# AWG_CPCIS_Connectors_P1_P6.net
KiCad netlist of a schematic drawn in Altium Designer
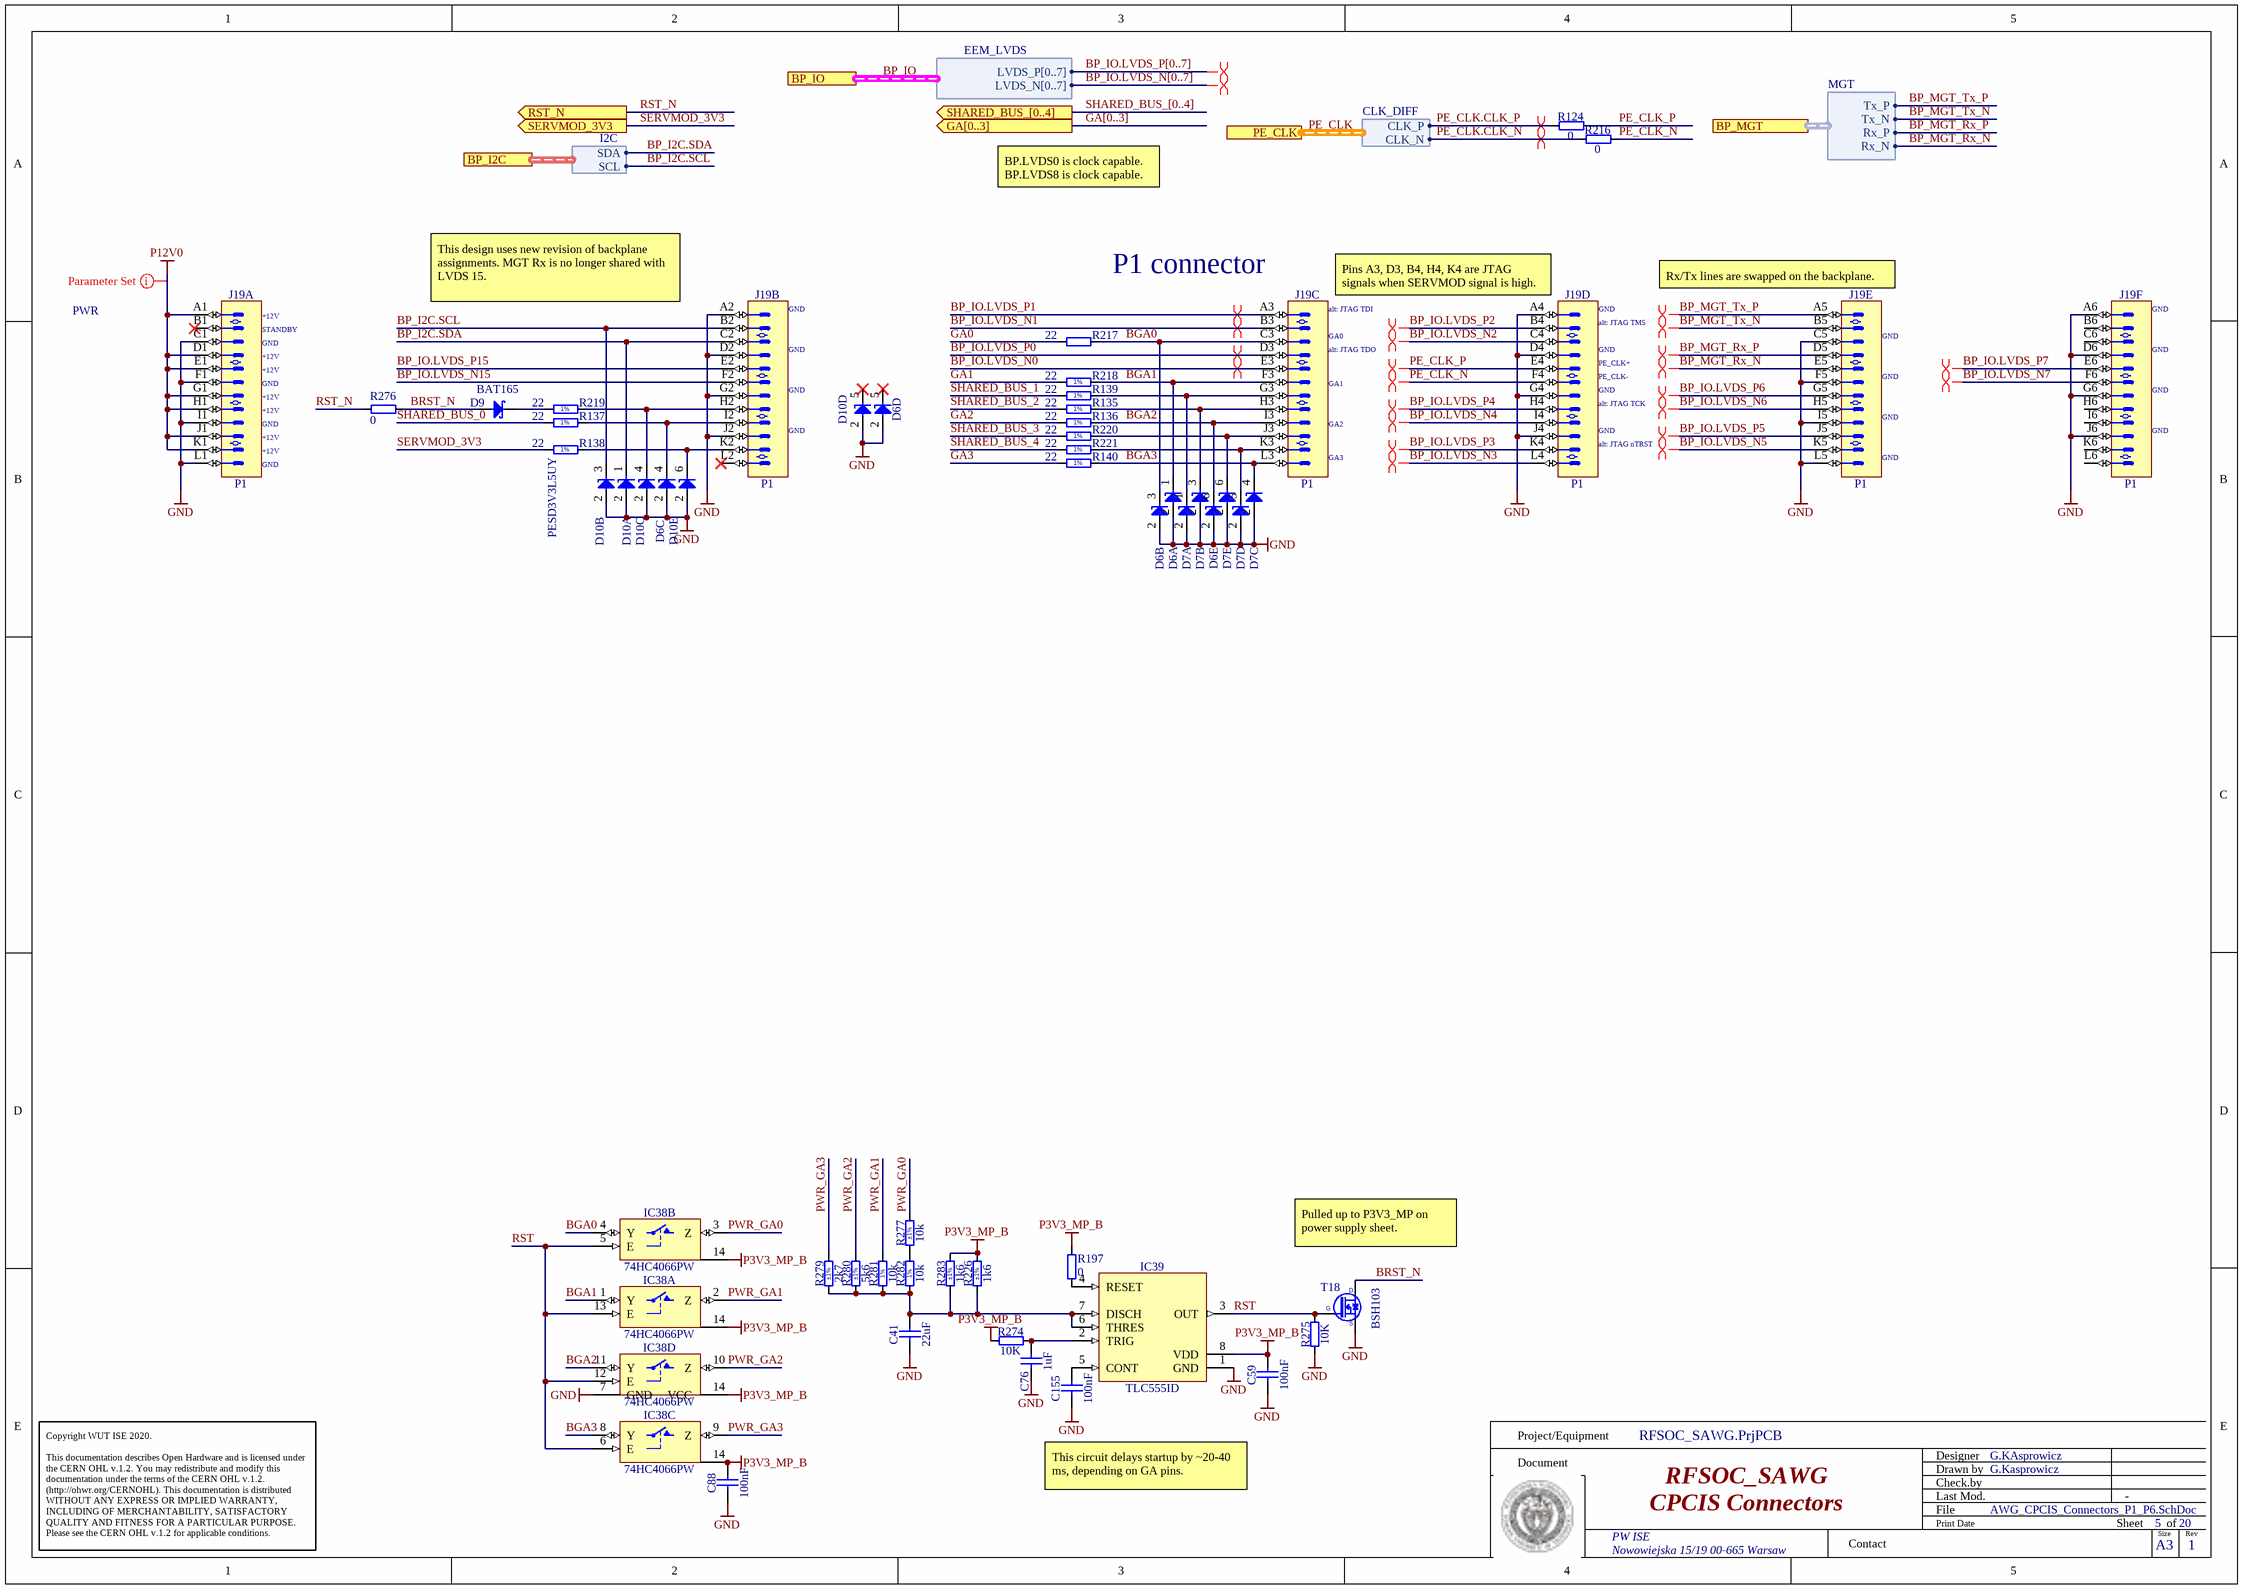
[diagram p0: AWG_CPCIS_Connectors_P1_P6.SchDoc]

(export (version "E")
  (design (tool "Eeschema 10.0.6"))
  (components
    (comp (ref "C41")
      (value "22uF")
      (footprint "CAPC1608X90N")
      (description "Non-polarised capacitor")
      (fields
        (field (name "MANUFACTURER") "GENERIC")
        (field (name "PART NUMBER") "CC0603_22UF_6.3V_20%_X5R")
        (field (name "AUTHOR") "CERN DEM JLC")
      )
      (libsource (lib "Capacitors") (part "Capacitor - non polarized"))
    )
    (comp (ref "C59")
      (value "100nF")
      (footprint "CAPC1005X55N")
      (description "Non-polarised capacitor")
      (fields
        (field (name "PART NUMBER") "CC0402_100NF_16V_10%_X5R")
        (field (name "VOLTAGE") "16V")
        (field (name "AUTHOR") "CERN DEM JLC")
      )
      (libsource (lib "Capacitors") (part "Capacitor - non polarized"))
    )
    (comp (ref "C76")
      (value "1uF")
      (footprint "CAPC1005X55N")
      (description "Non-polarised capacitor")
      (fields
        (field (name "PART NUMBER") "CC0402_1UF_16V_10%_X5R")
        (field (name "VOLTAGE") "16V")
        (field (name "AUTHOR") "CERN DEM JLC")
      )
      (libsource (lib "Capacitors") (part "Capacitor - non polarized"))
    )
    (comp (ref "C88")
      (value "100nF")
      (footprint "CAPC1005X55N")
      (description "Non-polarised capacitor")
      (fields
        (field (name "PART NUMBER") "CC0402_100NF_16V_10%_X5R")
        (field (name "VOLTAGE") "16V")
        (field (name "AUTHOR") "CERN DEM JLC")
      )
      (libsource (lib "Capacitors") (part "Capacitor - non polarized"))
    )
    (comp (ref "C155")
      (value "100nF")
      (footprint "CAPC1005X55N")
      (description "Non-polarised capacitor")
      (fields
        (field (name "PART NUMBER") "CC0402_100NF_16V_10%_X5R")
        (field (name "VOLTAGE") "16V")
        (field (name "AUTHOR") "CERN DEM JLC")
      )
      (libsource (lib "Capacitors") (part "Capacitor - non polarized"))
    )
    (comp (ref "D6")
      (value "PESD3V3L5UY")
      (footprint "SOT65P210X110-6N")
      (description "Fivefold ESD Protection Diode Arrays")
      (fields
        (field (name "VOLTAGE") "3.3V")
        (field (name "POWER") "200W")
        (field (name "AUTHOR") "CERN DEM WB")
      )
      (libsource (lib "ICs And Semiconductors") (part "PESD Array 5diodes 6pins Common anode2"))
    )
    (comp (ref "D7")
      (value "PESD3V3L5UY")
      (footprint "SOT65P210X110-6N")
      (description "Fivefold ESD Protection Diode Arrays")
      (fields
        (field (name "VOLTAGE") "3.3V")
        (field (name "POWER") "200W")
        (field (name "AUTHOR") "CERN DEM WB")
      )
      (libsource (lib "ICs And Semiconductors") (part "PESD Array 5diodes 6pins Common anode2"))
    )
    (comp (ref "D9")
      (value "BAT165")
      (footprint "SOD2512X110N")
      (description "Schottky Diode")
      (fields
        (field (name "MANUFACTURER") "INFINEON")
        (field (name "VOLTAGE") "40V")
        (field (name "AUTHOR") "CERN DEM JLC")
      )
      (libsource (lib "ICs And Semiconductors") (part "Diode Schottky"))
    )
    (comp (ref "D10")
      (value "PESD3V3L5UY")
      (footprint "SOT65P210X110-6N")
      (description "Fivefold ESD Protection Diode Arrays")
      (fields
        (field (name "VOLTAGE") "3.3V")
        (field (name "POWER") "200W")
        (field (name "AUTHOR") "CERN DEM WB")
      )
      (libsource (lib "ICs And Semiconductors") (part "PESD Array 5diodes 6pins Common anode2"))
    )
    (comp (ref "IC38")
      (value "74HC4066PW")
      (footprint "SOP65P640X110-14N")
      (fields (field (name "MANUFACTURER") "NXP SEMICONDUCTORS") (field (name "AUTHOR") "CERN DEM JLC"))
      (libsource (lib "ICs And Semiconductors") (part "4066"))
    )
    (comp (ref "IC39")
      (value "TLC555ID")
      (footprint "SOIC127P600X175-8N")
      (description "LinCMOS Timer")
      (fields (field (name "MANUFACTURER") "TEXAS INSTRUMENTS") (field (name "AUTHOR") "CERN DEM JMW"))
      (libsource (lib "ICs And Semiconductors") (part "TLC555"))
    )
    (comp (ref "J19")
      (value "P1")
      (footprint "AMPHENOL_10052825-101LF")
      (description "72 Contacts Header, 6 Columns, 4 Pairs per Column")
      (fields
        (field (name "PART NUMBER") "AMPHENOL_10052825-101LF")
        (field (name "MANUFACTURER") "AMPHENOL")
        (field (name "AUTHOR") "CERN DEM MR")
      )
      (libsource (lib "Connectors") (part "AMPHENOL_10052825-101LF"))
    )
    (comp (ref "R124")
      (value "0")
      (footprint "RESC0603X28N")
      (description "Resistor")
      (fields
        (field (name "PART NUMBER") "R0201_0R_JUMPER")
        (field (name "MANUFACTURER") "GENERIC")
        (field (name "AUTHOR") "CERN DEM JLC")
      )
      (libsource (lib "Resistors") (part "Resistor"))
    )
    (comp (ref "R135")
      (value "22")
      (footprint "RESC1005X40N")
      (description "Resistor - 1%")
      (fields
        (field (name "PART NUMBER") "R0402_22R_1%_0.0625W_100PPM")
        (field (name "POWER") "0.0625W")
        (field (name "AUTHOR") "CERN DEM JLC")
      )
      (libsource (lib "Resistors") (part "Resistor - 1%"))
    )
    (comp (ref "R136")
      (value "22")
      (footprint "RESC1005X40N")
      (description "Resistor - 1%")
      (fields
        (field (name "PART NUMBER") "R0402_22R_1%_0.0625W_100PPM")
        (field (name "POWER") "0.0625W")
        (field (name "AUTHOR") "CERN DEM JLC")
      )
      (libsource (lib "Resistors") (part "Resistor - 1%"))
    )
    (comp (ref "R137")
      (value "22")
      (footprint "RESC1005X40N")
      (description "Resistor - 1%")
      (fields
        (field (name "PART NUMBER") "R0402_22R_1%_0.0625W_100PPM")
        (field (name "POWER") "0.0625W")
        (field (name "AUTHOR") "CERN DEM JLC")
      )
      (libsource (lib "Resistors") (part "Resistor - 1%"))
    )
    (comp (ref "R138")
      (value "22")
      (footprint "RESC1005X40N")
      (description "Resistor - 1%")
      (fields
        (field (name "PART NUMBER") "R0402_22R_1%_0.0625W_100PPM")
        (field (name "POWER") "0.0625W")
        (field (name "AUTHOR") "CERN DEM JLC")
      )
      (libsource (lib "Resistors") (part "Resistor - 1%"))
    )
    (comp (ref "R139")
      (value "22")
      (footprint "RESC1005X40N")
      (description "Resistor - 1%")
      (fields
        (field (name "PART NUMBER") "R0402_22R_1%_0.0625W_100PPM")
        (field (name "POWER") "0.0625W")
        (field (name "AUTHOR") "CERN DEM JLC")
      )
      (libsource (lib "Resistors") (part "Resistor - 1%"))
    )
    (comp (ref "R140")
      (value "22")
      (footprint "RESC1005X40N")
      (description "Resistor - 1%")
      (fields
        (field (name "PART NUMBER") "R0402_22R_1%_0.0625W_100PPM")
        (field (name "POWER") "0.0625W")
        (field (name "AUTHOR") "CERN DEM JLC")
      )
      (libsource (lib "Resistors") (part "Resistor - 1%"))
    )
    (comp (ref "R197")
      (value "0")
      (footprint "RESC1005X40N")
      (description "Resistor")
      (fields
        (field (name "PART NUMBER") "R0402_0R_JUMPER")
        (field (name "MANUFACTURER") "GENERIC")
        (field (name "AUTHOR") "CERN DEM JLC")
      )
      (libsource (lib "Resistors") (part "Resistor"))
    )
    (comp (ref "R216")
      (value "0")
      (footprint "RESC0603X28N")
      (description "Resistor")
      (fields
        (field (name "PART NUMBER") "R0201_0R_JUMPER")
        (field (name "MANUFACTURER") "GENERIC")
        (field (name "AUTHOR") "CERN DEM JLC")
      )
      (libsource (lib "Resistors") (part "Resistor"))
    )
    (comp (ref "R217")
      (value "22")
      (footprint "RESC1005X40N")
      (description "Resistor - 1%")
      (fields
        (field (name "PART NUMBER") "R0402_22R_1%_0.0625W_100PPM")
        (field (name "POWER") "0.0625W")
        (field (name "AUTHOR") "CERN DEM JLC")
      )
      (libsource (lib "Resistors") (part "Resistor - 1%"))
    )
    (comp (ref "R218")
      (value "22")
      (footprint "RESC1005X40N")
      (description "Resistor - 1%")
      (fields
        (field (name "PART NUMBER") "R0402_22R_1%_0.0625W_100PPM")
        (field (name "POWER") "0.0625W")
        (field (name "AUTHOR") "CERN DEM JLC")
      )
      (libsource (lib "Resistors") (part "Resistor - 1%"))
    )
    (comp (ref "R219")
      (value "22")
      (footprint "RESC1005X40N")
      (description "Resistor - 1%")
      (fields
        (field (name "PART NUMBER") "R0402_22R_1%_0.0625W_100PPM")
        (field (name "POWER") "0.0625W")
        (field (name "AUTHOR") "CERN DEM JLC")
      )
      (libsource (lib "Resistors") (part "Resistor - 1%"))
    )
    (comp (ref "R220")
      (value "22")
      (footprint "RESC1005X40N")
      (description "Resistor - 1%")
      (fields
        (field (name "PART NUMBER") "R0402_22R_1%_0.0625W_100PPM")
        (field (name "POWER") "0.0625W")
        (field (name "AUTHOR") "CERN DEM JLC")
      )
      (libsource (lib "Resistors") (part "Resistor - 1%"))
    )
    (comp (ref "R221")
      (value "22")
      (footprint "RESC1005X40N")
      (description "Resistor - 1%")
      (fields
        (field (name "PART NUMBER") "R0402_22R_1%_0.0625W_100PPM")
        (field (name "POWER") "0.0625W")
        (field (name "AUTHOR") "CERN DEM JLC")
      )
      (libsource (lib "Resistors") (part "Resistor - 1%"))
    )
    (comp (ref "R226")
      (value "1k6")
      (footprint "RESC1005X40N")
      (description "Resistor - 1%")
      (fields
        (field (name "PART NUMBER") "R0402_1K6_1%_0.0625W_100PPM")
        (field (name "POWER") "0.0625W")
        (field (name "TOLERANCE") "±1%")
        (field (name "AUTHOR") "CERN DEM JLC")
      )
      (libsource (lib "Resistors") (part "Resistor - 1%"))
    )
    (comp (ref "R274")
      (value "10K")
      (footprint "RESC1005X40N")
      (description "Resistor - 1%")
      (fields
        (field (name "PART NUMBER") "R0402_10K_1%_0.0625W_100PPM")
        (field (name "POWER") "0.0625W")
        (field (name "AUTHOR") "CERN DEM JLC")
      )
      (libsource (lib "Resistors") (part "Resistor - 1%"))
    )
    (comp (ref "R275")
      (value "10K")
      (footprint "RESC1005X40N")
      (description "Resistor - 1%")
      (fields
        (field (name "PART NUMBER") "R0402_10K_1%_0.0625W_100PPM")
        (field (name "POWER") "0.0625W")
        (field (name "AUTHOR") "CERN DEM JLC")
      )
      (libsource (lib "Resistors") (part "Resistor - 1%"))
    )
    (comp (ref "R276")
      (value "0")
      (footprint "RESC1005X40N")
      (description "Resistor")
      (fields
        (field (name "PART NUMBER") "R0402_0R_JUMPER")
        (field (name "MANUFACTURER") "GENERIC")
        (field (name "AUTHOR") "CERN DEM JLC")
      )
      (libsource (lib "Resistors") (part "Resistor"))
    )
    (comp (ref "R277")
      (value "10k")
      (footprint "RESC1005X40N")
      (description "Resistor - 1%")
      (fields
        (field (name "PART NUMBER") "R0402_10K_1%_0.0625W_100PPM")
        (field (name "POWER") "0.0625W")
        (field (name "TOLERANCE") "±1%")
        (field (name "AUTHOR") "CERN DEM JLC")
      )
      (libsource (lib "Resistors") (part "Resistor - 1%"))
    )
    (comp (ref "R279")
      (value "2k7")
      (footprint "RESC1608X55N")
      (description "Resistor - 1%")
      (fields
        (field (name "PART NUMBER") "R0603_2K7_1%_0.1W_100PPM")
        (field (name "POWER") "0.1W")
        (field (name "TOLERANCE") "±1%")
        (field (name "AUTHOR") "CERN DEM JLC")
      )
      (libsource (lib "") (part "Resistor - 1%_1"))
    )
    (comp (ref "R280")
      (value "5k6")
      (footprint "RESC1005X40N")
      (description "Resistor - 1%")
      (fields
        (field (name "PART NUMBER") "R0402_5K6_1%_0.0625W_100PPM")
        (field (name "POWER") "0.0625W")
        (field (name "TOLERANCE") "±1%")
        (field (name "AUTHOR") "CERN DEM JLC")
      )
      (libsource (lib "Resistors") (part "Resistor - 1%"))
    )
    (comp (ref "R281")
      (value "10k")
      (footprint "RESC1005X40N")
      (description "Resistor - 1%")
      (fields
        (field (name "PART NUMBER") "R0402_1K_1%_0.0625W_100PPM")
        (field (name "POWER") "0.0625W")
        (field (name "AUTHOR") "CERN DEM JLC")
      )
      (libsource (lib "Resistors") (part "Resistor - 1%"))
    )
    (comp (ref "R282")
      (value "10k")
      (footprint "RESC1005X40N")
      (description "Resistor - 1%")
      (fields
        (field (name "PART NUMBER") "R0402_1K_1%_0.0625W_100PPM")
        (field (name "POWER") "0.0625W")
        (field (name "AUTHOR") "CERN DEM JLC")
      )
      (libsource (lib "Resistors") (part "Resistor - 1%"))
    )
    (comp (ref "R283")
      (value "1k6")
      (footprint "RESC1005X40N")
      (description "Resistor - 1%")
      (fields
        (field (name "PART NUMBER") "R0402_1K6_1%_0.0625W_100PPM")
        (field (name "POWER") "0.0625W")
        (field (name "TOLERANCE") "±1%")
        (field (name "AUTHOR") "CERN DEM JLC")
      )
      (libsource (lib "Resistors") (part "Resistor - 1%"))
    )
    (comp (ref "T18")
      (value "BSH103")
      (footprint "SOT95P230X110-3N")
      (description "N-CHANNEL MOSFET WITH DIODE")
      (fields (field (name "MANUFACTURER") "NEXPERIA") (field (name "AUTHOR") "CERN DEM JLC"))
      (libsource (lib "ICs And Semiconductors") (part "N-MOSFET-D 1G 2S 3D"))
    )
  )
  (nets
    (net (code "5") (name "/BGA0") (class "Default")
      (node (ref "D6") (pin "3") (pinfunction "C_3") (pintype "passive"))
      (node (ref "IC38") (pin "4") (pinfunction "Y_4") (pintype "bidirectional"))
      (node (ref "J19") (pin "C3") (pinfunction "C3_C3") (pintype "bidirectional"))
      (node (ref "R217") (pin "2") (pinfunction "2_2") (pintype "passive"))
    )
    (net (code "6") (name "/BGA1") (class "Default")
      (node (ref "D6") (pin "1") (pinfunction "C_1") (pintype "passive"))
      (node (ref "IC38") (pin "1") (pinfunction "Y_1") (pintype "bidirectional"))
      (node (ref "J19") (pin "F3") (pinfunction "F3_F3") (pintype "bidirectional"))
      (node (ref "R218") (pin "2") (pinfunction "2_2") (pintype "passive"))
    )
    (net (code "7") (name "/BGA2") (class "Default")
      (node (ref "D6") (pin "6") (pinfunction "C_6") (pintype "passive"))
      (node (ref "IC38") (pin "11") (pinfunction "Y_11") (pintype "bidirectional"))
      (node (ref "J19") (pin "I3") (pinfunction "I3_I3") (pintype "bidirectional"))
      (node (ref "R136") (pin "2") (pinfunction "2_2") (pintype "passive"))
    )
    (net (code "8") (name "/BGA3") (class "Default")
      (node (ref "D7") (pin "4") (pinfunction "C_4") (pintype "passive"))
      (node (ref "IC38") (pin "8") (pinfunction "Y_8") (pintype "bidirectional"))
      (node (ref "J19") (pin "L3") (pinfunction "L3_L3") (pintype "bidirectional"))
      (node (ref "R140") (pin "2") (pinfunction "2_2") (pintype "passive"))
    )
    (net (code "9") (name "/BP_I2C.SCL") (class "Default")
      (node (ref "D10") (pin "3") (pinfunction "C_3") (pintype "passive"))
      (node (ref "J19") (pin "B2") (pinfunction "B2_B2") (pintype "bidirectional"))
    )
    (net (code "10") (name "/BP_I2C.SDA") (class "Default")
      (node (ref "D10") (pin "1") (pinfunction "C_1") (pintype "passive"))
      (node (ref "J19") (pin "C2") (pinfunction "C2_C2") (pintype "bidirectional"))
    )
    (net (code "11") (name "/BP_IO.LVDS_N0") (class "Default")
      (node (ref "J19") (pin "E3") (pinfunction "E3_E3") (pintype "bidirectional"))
    )
    (net (code "12") (name "/BP_IO.LVDS_N1") (class "Default")
      (node (ref "J19") (pin "B3") (pinfunction "B3_B3") (pintype "bidirectional"))
    )
    (net (code "13") (name "/BP_IO.LVDS_N2") (class "Default")
      (node (ref "J19") (pin "C4") (pinfunction "C4_C4") (pintype "bidirectional"))
    )
    (net (code "14") (name "/BP_IO.LVDS_N3") (class "Default")
      (node (ref "J19") (pin "L4") (pinfunction "L4_L4") (pintype "bidirectional"))
    )
    (net (code "15") (name "/BP_IO.LVDS_N4") (class "Default")
      (node (ref "J19") (pin "I4") (pinfunction "I4_I4") (pintype "bidirectional"))
    )
    (net (code "16") (name "/BP_IO.LVDS_N5") (class "Default")
      (node (ref "J19") (pin "K5") (pinfunction "K5_K5") (pintype "bidirectional"))
    )
    (net (code "17") (name "/BP_IO.LVDS_N6") (class "Default")
      (node (ref "J19") (pin "H5") (pinfunction "H5_H5") (pintype "bidirectional"))
    )
    (net (code "18") (name "/BP_IO.LVDS_N7") (class "Default")
      (node (ref "J19") (pin "F6") (pinfunction "F6_F6") (pintype "bidirectional"))
    )
    (net (code "19") (name "/BP_IO.LVDS_N15") (class "Default")
      (node (ref "J19") (pin "F2") (pinfunction "F2_F2") (pintype "bidirectional"))
    )
    (net (code "20") (name "/BP_IO.LVDS_P0") (class "Default")
      (node (ref "J19") (pin "D3") (pinfunction "D3_D3") (pintype "bidirectional"))
    )
    (net (code "21") (name "/BP_IO.LVDS_P1") (class "Default")
      (node (ref "J19") (pin "A3") (pinfunction "A3_A3") (pintype "bidirectional"))
    )
    (net (code "22") (name "/BP_IO.LVDS_P2") (class "Default")
      (node (ref "J19") (pin "B4") (pinfunction "B4_B4") (pintype "bidirectional"))
    )
    (net (code "23") (name "/BP_IO.LVDS_P3") (class "Default")
      (node (ref "J19") (pin "K4") (pinfunction "K4_K4") (pintype "bidirectional"))
    )
    (net (code "24") (name "/BP_IO.LVDS_P4") (class "Default")
      (node (ref "J19") (pin "H4") (pinfunction "H4_H4") (pintype "bidirectional"))
    )
    (net (code "25") (name "/BP_IO.LVDS_P5") (class "Default")
      (node (ref "J19") (pin "J5") (pinfunction "J5_J5") (pintype "bidirectional"))
    )
    (net (code "26") (name "/BP_IO.LVDS_P6") (class "Default")
      (node (ref "J19") (pin "G5") (pinfunction "G5_G5") (pintype "bidirectional"))
    )
    (net (code "27") (name "/BP_IO.LVDS_P7") (class "Default")
      (node (ref "J19") (pin "E6") (pinfunction "E6_E6") (pintype "bidirectional"))
    )
    (net (code "28") (name "/BP_IO.LVDS_P15") (class "Default")
      (node (ref "J19") (pin "E2") (pinfunction "E2_E2") (pintype "bidirectional"))
    )
    (net (code "30") (name "/BP_MGT_Rx_N") (class "Default")
      (node (ref "J19") (pin "E5") (pinfunction "E5_E5") (pintype "bidirectional"))
    )
    (net (code "31") (name "/BP_MGT_Rx_P") (class "Default")
      (node (ref "J19") (pin "D5") (pinfunction "D5_D5") (pintype "bidirectional"))
    )
    (net (code "32") (name "/BP_MGT_Tx_N") (class "Default")
      (node (ref "J19") (pin "B5") (pinfunction "B5_B5") (pintype "bidirectional"))
    )
    (net (code "33") (name "/BP_MGT_Tx_P") (class "Default")
      (node (ref "J19") (pin "A5") (pinfunction "A5_A5") (pintype "bidirectional"))
    )
    (net (code "34") (name "/BRST_N") (class "Default")
      (node (ref "D9") (pin "2") (pinfunction "A_2") (pintype "passive"))
      (node (ref "R276") (pin "1") (pinfunction "1_1") (pintype "passive"))
      (node (ref "T18") (pin "3") (pinfunction "D_3") (pintype "passive"))
    )
    (net (code "35") (name "/GA0") (class "Default")
      (node (ref "R217") (pin "1") (pinfunction "1_1") (pintype "passive"))
    )
    (net (code "36") (name "/GA1") (class "Default")
      (node (ref "R218") (pin "1") (pinfunction "1_1") (pintype "passive"))
    )
    (net (code "37") (name "/GA2") (class "Default")
      (node (ref "R136") (pin "1") (pinfunction "1_1") (pintype "passive"))
    )
    (net (code "38") (name "/GA3") (class "Default")
      (node (ref "R140") (pin "1") (pinfunction "1_1") (pintype "passive"))
    )
    (net (code "40") (name "/PE_CLK.CLK_N") (class "Default")
      (node (ref "R216") (pin "1") (pinfunction "1_1") (pintype "passive"))
    )
    (net (code "41") (name "/PE_CLK.CLK_P") (class "Default")
      (node (ref "R124") (pin "1") (pinfunction "1_1") (pintype "passive"))
    )
    (net (code "42") (name "/PE_CLK_N") (class "Default")
      (node (ref "J19") (pin "F4") (pinfunction "F4_F4") (pintype "bidirectional"))
      (node (ref "R216") (pin "2") (pinfunction "2_2") (pintype "passive"))
    )
    (net (code "43") (name "/PE_CLK_P") (class "Default")
      (node (ref "J19") (pin "E4") (pinfunction "E4_E4") (pintype "bidirectional"))
      (node (ref "R124") (pin "2") (pinfunction "2_2") (pintype "passive"))
    )
    (net (code "45") (name "/PWR_GA0") (class "Default")
      (node (ref "IC38") (pin "3") (pinfunction "Z_3") (pintype "bidirectional"))
      (node (ref "R277") (pin "2") (pinfunction "2_2") (pintype "passive"))
    )
    (net (code "46") (name "/PWR_GA1") (class "Default")
      (node (ref "IC38") (pin "2") (pinfunction "Z_2") (pintype "bidirectional"))
      (node (ref "R281") (pin "2") (pinfunction "2_2") (pintype "passive"))
    )
    (net (code "47") (name "/PWR_GA2") (class "Default")
      (node (ref "IC38") (pin "10") (pinfunction "Z_10") (pintype "bidirectional"))
      (node (ref "R280") (pin "2") (pinfunction "2_2") (pintype "passive"))
    )
    (net (code "48") (name "/PWR_GA3") (class "Default")
      (node (ref "IC38") (pin "9") (pinfunction "Z_9") (pintype "bidirectional"))
      (node (ref "R279") (pin "2") (pinfunction "2_2") (pintype "passive"))
    )
    (net (code "49") (name "/RST") (class "Default")
      (node (ref "IC38") (pin "12") (pinfunction "E_12") (pintype "input"))
      (node (ref "IC38") (pin "13") (pinfunction "E_13") (pintype "input"))
      (node (ref "IC38") (pin "5") (pinfunction "E_5") (pintype "input"))
      (node (ref "IC38") (pin "6") (pinfunction "E_6") (pintype "input"))
      (node (ref "IC39") (pin "3") (pinfunction "OUT_3") (pintype "output"))
      (node (ref "R275") (pin "2") (pinfunction "2_2") (pintype "passive"))
      (node (ref "T18") (pin "1") (pinfunction "G_1") (pintype "passive"))
    )
    (net (code "50") (name "/RST_N") (class "Default")
      (node (ref "R276") (pin "2") (pinfunction "2_2") (pintype "passive"))
    )
    (net (code "51") (name "/SERVMOD_3V3") (class "Default")
      (node (ref "R138") (pin "1") (pinfunction "1_1") (pintype "passive"))
    )
    (net (code "52") (name "/SHARED_BUS_0") (class "Default")
      (node (ref "R137") (pin "1") (pinfunction "1_1") (pintype "passive"))
    )
    (net (code "53") (name "/SHARED_BUS_1") (class "Default")
      (node (ref "R139") (pin "1") (pinfunction "1_1") (pintype "passive"))
    )
    (net (code "54") (name "/SHARED_BUS_2") (class "Default")
      (node (ref "R135") (pin "1") (pinfunction "1_1") (pintype "passive"))
    )
    (net (code "55") (name "/SHARED_BUS_3") (class "Default")
      (node (ref "R220") (pin "1") (pinfunction "1_1") (pintype "passive"))
    )
    (net (code "56") (name "/SHARED_BUS_4") (class "Default")
      (node (ref "R221") (pin "1") (pinfunction "1_1") (pintype "passive"))
    )
    (net (code "61") (name "GND") (class "Default")
      (node (ref "C155") (pin "1") (pinfunction "1_1") (pintype "passive"))
      (node (ref "C41") (pin "1") (pinfunction "1_1") (pintype "passive"))
      (node (ref "C59") (pin "1") (pinfunction "1_1") (pintype "passive"))
      (node (ref "C76") (pin "1") (pinfunction "1_1") (pintype "passive"))
      (node (ref "C88") (pin "1") (pinfunction "1_1") (pintype "passive"))
      (node (ref "D10") (pin "2") (pinfunction "A_2") (pintype "passive"))
      (node (ref "D6") (pin "2") (pinfunction "A_2") (pintype "passive"))
      (node (ref "D7") (pin "2") (pinfunction "A_2") (pintype "passive"))
      (node (ref "IC38") (pin "7") (pinfunction "GND_7") (pintype "power_in"))
      (node (ref "IC39") (pin "1") (pinfunction "GND_1") (pintype "power_in"))
      (node (ref "J19") (pin "A2") (pinfunction "A2_A2") (pintype "bidirectional"))
      (node (ref "J19") (pin "A4") (pinfunction "A4_A4") (pintype "bidirectional"))
      (node (ref "J19") (pin "A6") (pinfunction "A6_A6") (pintype "bidirectional"))
      (node (ref "J19") (pin "C1") (pinfunction "C1_C1") (pintype "bidirectional"))
      (node (ref "J19") (pin "C5") (pinfunction "C5_C5") (pintype "bidirectional"))
      (node (ref "J19") (pin "D2") (pinfunction "D2_D2") (pintype "bidirectional"))
      (node (ref "J19") (pin "D4") (pinfunction "D4_D4") (pintype "bidirectional"))
      (node (ref "J19") (pin "D6") (pinfunction "D6_D6") (pintype "bidirectional"))
      (node (ref "J19") (pin "F1") (pinfunction "F1_F1") (pintype "bidirectional"))
      (node (ref "J19") (pin "F5") (pinfunction "F5_F5") (pintype "bidirectional"))
      (node (ref "J19") (pin "G2") (pinfunction "G2_G2") (pintype "bidirectional"))
      (node (ref "J19") (pin "G4") (pinfunction "G4_G4") (pintype "bidirectional"))
      (node (ref "J19") (pin "G6") (pinfunction "G6_G6") (pintype "bidirectional"))
      (node (ref "J19") (pin "I1") (pinfunction "I1_I1") (pintype "bidirectional"))
      (node (ref "J19") (pin "I5") (pinfunction "I5_I5") (pintype "bidirectional"))
      (node (ref "J19") (pin "J2") (pinfunction "J2_J2") (pintype "bidirectional"))
      (node (ref "J19") (pin "J4") (pinfunction "J4_J4") (pintype "bidirectional"))
      (node (ref "J19") (pin "J6") (pinfunction "J6_J6") (pintype "bidirectional"))
      (node (ref "J19") (pin "L1") (pinfunction "L1_L1") (pintype "bidirectional"))
      (node (ref "J19") (pin "L5") (pinfunction "L5_L5") (pintype "bidirectional"))
      (node (ref "R275") (pin "1") (pinfunction "1_1") (pintype "passive"))
      (node (ref "T18") (pin "2") (pinfunction "S_2") (pintype "passive"))
    )
    (net (code "62") (name "Net-(D6C-C)") (class "Default")
      (node (ref "D6") (pin "4") (pinfunction "C_4") (pintype "passive"))
      (node (ref "J19") (pin "I2") (pinfunction "I2_I2") (pintype "bidirectional"))
      (node (ref "R137") (pin "2") (pinfunction "2_2") (pintype "passive"))
    )
    (net (code "63") (name "Net-(D7A-C)") (class "Default")
      (node (ref "D7") (pin "1") (pinfunction "C_1") (pintype "passive"))
      (node (ref "J19") (pin "G3") (pinfunction "G3_G3") (pintype "bidirectional"))
      (node (ref "R139") (pin "2") (pinfunction "2_2") (pintype "passive"))
    )
    (net (code "64") (name "Net-(D7B-C)") (class "Default")
      (node (ref "D7") (pin "3") (pinfunction "C_3") (pintype "passive"))
      (node (ref "J19") (pin "H3") (pinfunction "H3_H3") (pintype "bidirectional"))
      (node (ref "R135") (pin "2") (pinfunction "2_2") (pintype "passive"))
    )
    (net (code "65") (name "Net-(D7D-C)") (class "Default")
      (node (ref "D7") (pin "5") (pinfunction "C_5") (pintype "passive"))
      (node (ref "J19") (pin "K3") (pinfunction "K3_K3") (pintype "bidirectional"))
      (node (ref "R221") (pin "2") (pinfunction "2_2") (pintype "passive"))
    )
    (net (code "66") (name "Net-(D7E-C)") (class "Default")
      (node (ref "D7") (pin "6") (pinfunction "C_6") (pintype "passive"))
      (node (ref "J19") (pin "J3") (pinfunction "J3_J3") (pintype "bidirectional"))
      (node (ref "R220") (pin "2") (pinfunction "2_2") (pintype "passive"))
    )
    (net (code "67") (name "Net-(D9-C)") (class "Default")
      (node (ref "D9") (pin "1") (pinfunction "C_1") (pintype "passive"))
      (node (ref "R219") (pin "1") (pinfunction "1_1") (pintype "passive"))
    )
    (net (code "68") (name "Net-(D10C-C)") (class "Default")
      (node (ref "D10") (pin "4") (pinfunction "C_4") (pintype "passive"))
      (node (ref "J19") (pin "H2") (pinfunction "H2_H2") (pintype "bidirectional"))
      (node (ref "R219") (pin "2") (pinfunction "2_2") (pintype "passive"))
    )
    (net (code "69") (name "Net-(D10E-C)") (class "Default")
      (node (ref "D10") (pin "6") (pinfunction "C_6") (pintype "passive"))
      (node (ref "J19") (pin "K2") (pinfunction "K2_K2") (pintype "bidirectional"))
      (node (ref "R138") (pin "2") (pinfunction "2_2") (pintype "passive"))
    )
    (net (code "70") (name "Net-(IC39-CONT)") (class "Default")
      (node (ref "C155") (pin "2") (pinfunction "2_2") (pintype "passive"))
      (node (ref "IC39") (pin "5") (pinfunction "CONT_5") (pintype "input"))
    )
    (net (code "71") (name "Net-(IC39-DISCH)") (class "Default")
      (node (ref "C41") (pin "2") (pinfunction "2_2") (pintype "passive"))
      (node (ref "IC39") (pin "6") (pinfunction "THRES_6") (pintype "input"))
      (node (ref "IC39") (pin "7") (pinfunction "DISCH_7") (pintype "input"))
      (node (ref "R226") (pin "1") (pinfunction "1_1") (pintype "passive"))
      (node (ref "R279") (pin "1") (pinfunction "1_1") (pintype "passive"))
      (node (ref "R280") (pin "1") (pinfunction "1_1") (pintype "passive"))
      (node (ref "R281") (pin "1") (pinfunction "1_1") (pintype "passive"))
      (node (ref "R282") (pin "1") (pinfunction "1_1") (pintype "passive"))
      (node (ref "R283") (pin "1") (pinfunction "1_1") (pintype "passive"))
    )
    (net (code "72") (name "Net-(IC39-RESET)") (class "Default")
      (node (ref "IC39") (pin "4") (pinfunction "RESET_4") (pintype "input"))
      (node (ref "R197") (pin "1") (pinfunction "1_1") (pintype "passive"))
    )
    (net (code "73") (name "Net-(IC39-TRIG)") (class "Default")
      (node (ref "C76") (pin "2") (pinfunction "2_2") (pintype "passive"))
      (node (ref "IC39") (pin "2") (pinfunction "TRIG_2") (pintype "input"))
      (node (ref "R274") (pin "2") (pinfunction "2_2") (pintype "passive"))
    )
    (net (code "74") (name "Net-(R277-Pad1)") (class "Default")
      (node (ref "R277") (pin "1") (pinfunction "1_1") (pintype "passive"))
      (node (ref "R282") (pin "2") (pinfunction "2_2") (pintype "passive"))
    )
    (net (code "75") (name "P3V3_MP_B") (class "Default")
      (node (ref "C59") (pin "2") (pinfunction "2_2") (pintype "passive"))
      (node (ref "C88") (pin "2") (pinfunction "2_2") (pintype "passive"))
      (node (ref "IC38") (pin "14") (pinfunction "VCC_14") (pintype "power_in"))
      (node (ref "IC39") (pin "8") (pinfunction "VDD_8") (pintype "power_in"))
      (node (ref "R197") (pin "2") (pinfunction "2_2") (pintype "passive"))
      (node (ref "R226") (pin "2") (pinfunction "2_2") (pintype "passive"))
      (node (ref "R274") (pin "1") (pinfunction "1_1") (pintype "passive"))
      (node (ref "R283") (pin "2") (pinfunction "2_2") (pintype "passive"))
    )
    (net (code "76") (name "P12V0") (class "Default")
      (node (ref "J19") (pin "A1") (pinfunction "A1_A1") (pintype "bidirectional"))
      (node (ref "J19") (pin "D1") (pinfunction "D1_D1") (pintype "bidirectional"))
      (node (ref "J19") (pin "E1") (pinfunction "E1_E1") (pintype "bidirectional"))
      (node (ref "J19") (pin "G1") (pinfunction "G1_G1") (pintype "bidirectional"))
      (node (ref "J19") (pin "H1") (pinfunction "H1_H1") (pintype "bidirectional"))
      (node (ref "J19") (pin "J1") (pinfunction "J1_J1") (pintype "bidirectional"))
      (node (ref "J19") (pin "K1") (pinfunction "K1_K1") (pintype "bidirectional"))
    )
    (net (code "77") (name "unconnected-(D6D-C-Pad5)") (class "Default")
      (node (ref "D6") (pin "5") (pinfunction "C_5") (pintype "passive+no_connect"))
    )
    (net (code "78") (name "unconnected-(D10D-C-Pad5)") (class "Default")
      (node (ref "D10") (pin "5") (pinfunction "C_5") (pintype "passive+no_connect"))
    )
    (net (code "79") (name "unconnected-(J19-PadB1)") (class "Default")
      (node (ref "J19") (pin "B1") (pinfunction "B1_B1") (pintype "bidirectional+no_connect"))
    )
    (net (code "80") (name "unconnected-(J19-PadB6)") (class "Default")
      (node (ref "J19") (pin "B6") (pinfunction "B6_B6") (pintype "bidirectional"))
    )
    (net (code "81") (name "unconnected-(J19-PadC6)") (class "Default")
      (node (ref "J19") (pin "C6") (pinfunction "C6_C6") (pintype "bidirectional"))
    )
    (net (code "82") (name "unconnected-(J19-PadH6)") (class "Default")
      (node (ref "J19") (pin "H6") (pinfunction "H6_H6") (pintype "bidirectional"))
    )
    (net (code "83") (name "unconnected-(J19-PadI6)") (class "Default")
      (node (ref "J19") (pin "I6") (pinfunction "I6_I6") (pintype "bidirectional"))
    )
    (net (code "84") (name "unconnected-(J19-PadK6)") (class "Default")
      (node (ref "J19") (pin "K6") (pinfunction "K6_K6") (pintype "bidirectional"))
    )
    (net (code "85") (name "unconnected-(J19-PadL2)") (class "Default")
      (node (ref "J19") (pin "L2") (pinfunction "L2_L2") (pintype "bidirectional+no_connect"))
    )
    (net (code "86") (name "unconnected-(J19-PadL6)") (class "Default")
      (node (ref "J19") (pin "L6") (pinfunction "L6_L6") (pintype "bidirectional"))
    )
  )
)
